# USBFX2LP_2.net
KiCad netlist of a schematic drawn in Altium Designer
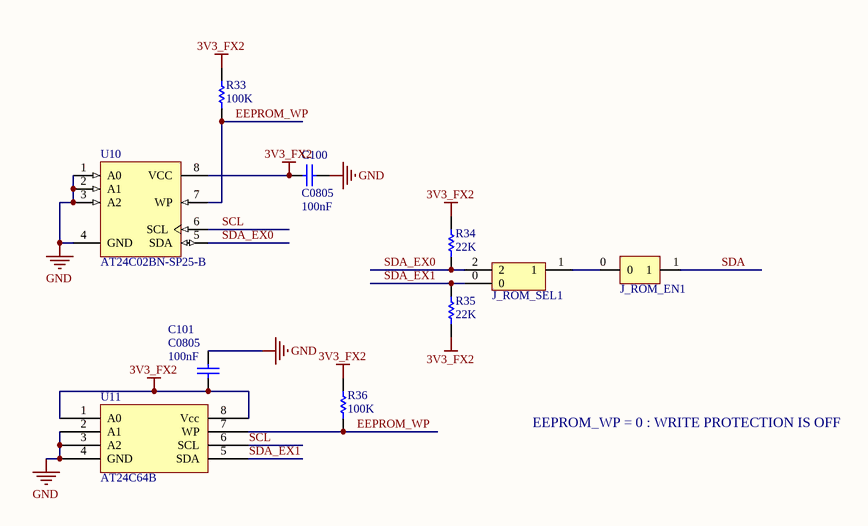
[diagram p0: USBFX2LP_2.SchDoc]

(export (version "E")
  (design (tool "Eeschema 10.0.6"))
  (components
    (comp (ref "C100")
      (value "C0805")
      (footprint "0805")
      (description "Ceramic Chip Capacitor - Standard")
      (fields (field (name "ALTIUM_VALUE") "100nF") (field (name "PUBLISHER") "Altium Limited"))
      (libsource (lib "KEMET Chip Capacitor") (part "C0805"))
    )
    (comp (ref "C101")
      (value "C0805")
      (footprint "0805")
      (description "Ceramic Chip Capacitor - Standard")
      (fields (field (name "ALTIUM_VALUE") "100nF") (field (name "PUBLISHER") "Altium Limited"))
      (libsource (lib "KEMET Chip Capacitor") (part "C0805"))
    )
    (comp (ref "J_ROM_EN1") (value "2pin") (footprint "2PIN") (libsource (lib "jumper2o54mm") (part "2pin")))
    (comp (ref "J_ROM_SEL1") (value "3pin") (footprint "3PIN") (libsource (lib "jumper2o54mm") (part "3pin")))
    (comp (ref "R33")
      (value "100K")
      (footprint "ERA-0805")
      (fields (field (name "PUBLISHER") "Altium Limited"))
      (libsource (lib "Panasonic Resistor") (part "ERA6Y"))
    )
    (comp (ref "R34")
      (value "22K")
      (footprint "ERA-0805")
      (fields (field (name "PUBLISHER") "Altium Limited"))
      (libsource (lib "Panasonic Resistor") (part "ERA6Y"))
    )
    (comp (ref "R35")
      (value "22K")
      (footprint "ERA-0805")
      (fields (field (name "PUBLISHER") "Altium Limited"))
      (libsource (lib "Panasonic Resistor") (part "ERA6Y"))
    )
    (comp (ref "R36")
      (value "100K")
      (footprint "ERA-0805")
      (fields (field (name "PUBLISHER") "Altium Limited"))
      (libsource (lib "Panasonic Resistor") (part "ERA6Y"))
    )
    (comp (ref "U10")
      (value "AT24C02BN-SP25-B")
      (footprint "8S1_N")
      (libsource (lib "Atmel Serial EEPROM") (part "AT24C02BN-SP25-B"))
    )
    (comp (ref "U11")
      (value "AT24C64B")
      (footprint "AT24C512B")
      (libsource (lib "AT24C512B_PRJCT") (part "AT24C512B SOIC8 PITCH 1.27"))
    )
  )
  (nets
    (net (code "1") (name "/EEPROM_WP") (class "Default")
      (node (ref "R33") (pin "2") (pinfunction "2_2") (pintype "passive"))
      (node (ref "R36") (pin "2") (pinfunction "2_2") (pintype "passive"))
      (node (ref "U10") (pin "7") (pinfunction "WP_7") (pintype "input"))
      (node (ref "U11") (pin "7") (pinfunction "WP_7") (pintype "passive"))
    )
    (net (code "2") (name "/SCL") (class "Default")
      (node (ref "U10") (pin "6") (pinfunction "SCL_6") (pintype "input"))
      (node (ref "U11") (pin "6") (pinfunction "SCL_6") (pintype "passive"))
    )
    (net (code "3") (name "/SDA") (class "Default")
      (node (ref "J_ROM_EN1") (pin "1") (pinfunction "1_1") (pintype "passive"))
    )
    (net (code "4") (name "/SDA_EX0") (class "Default")
      (node (ref "J_ROM_SEL1") (pin "2") (pinfunction "2_2") (pintype "passive"))
      (node (ref "R34") (pin "2") (pinfunction "2_2") (pintype "passive"))
      (node (ref "U10") (pin "5") (pinfunction "SDA_5") (pintype "bidirectional"))
    )
    (net (code "5") (name "/SDA_EX1") (class "Default")
      (node (ref "J_ROM_SEL1") (pin "0") (pinfunction "0_0") (pintype "passive"))
      (node (ref "R35") (pin "2") (pinfunction "2_2") (pintype "passive"))
      (node (ref "U11") (pin "5") (pinfunction "SDA_5") (pintype "passive"))
    )
    (net (code "6") (name "3V3_FX2") (class "Default")
      (node (ref "C100") (pin "2") (pinfunction "2_2") (pintype "passive"))
      (node (ref "C101") (pin "1") (pinfunction "1_1") (pintype "passive"))
      (node (ref "R33") (pin "1") (pinfunction "1_1") (pintype "passive"))
      (node (ref "R34") (pin "1") (pinfunction "1_1") (pintype "passive"))
      (node (ref "R35") (pin "1") (pinfunction "1_1") (pintype "passive"))
      (node (ref "R36") (pin "1") (pinfunction "1_1") (pintype "passive"))
      (node (ref "U10") (pin "8") (pinfunction "VCC_8") (pintype "power_in"))
      (node (ref "U11") (pin "1") (pinfunction "A0_1") (pintype "passive"))
      (node (ref "U11") (pin "8") (pinfunction "Vcc_8") (pintype "passive"))
    )
    (net (code "7") (name "GND") (class "Default")
      (node (ref "C100") (pin "1") (pinfunction "1_1") (pintype "passive"))
      (node (ref "C101") (pin "2") (pinfunction "2_2") (pintype "passive"))
      (node (ref "U10") (pin "1") (pinfunction "A0_1") (pintype "input"))
      (node (ref "U10") (pin "2") (pinfunction "A1_2") (pintype "input"))
      (node (ref "U10") (pin "3") (pinfunction "A2_3") (pintype "input"))
      (node (ref "U10") (pin "4") (pinfunction "GND_4") (pintype "power_in"))
      (node (ref "U11") (pin "2") (pinfunction "A1_2") (pintype "passive"))
      (node (ref "U11") (pin "3") (pinfunction "A2_3") (pintype "passive"))
      (node (ref "U11") (pin "4") (pinfunction "GND_4") (pintype "passive"))
    )
    (net (code "8") (name "Net-(J_ROM_EN1-Pad0)") (class "Default")
      (node (ref "J_ROM_EN1") (pin "0") (pinfunction "0_0") (pintype "passive"))
      (node (ref "J_ROM_SEL1") (pin "1") (pinfunction "1_1") (pintype "passive"))
    )
  )
)
